# SNES_and_NES_Dumper.net
KiCad netlist of a schematic drawn in EAGLE
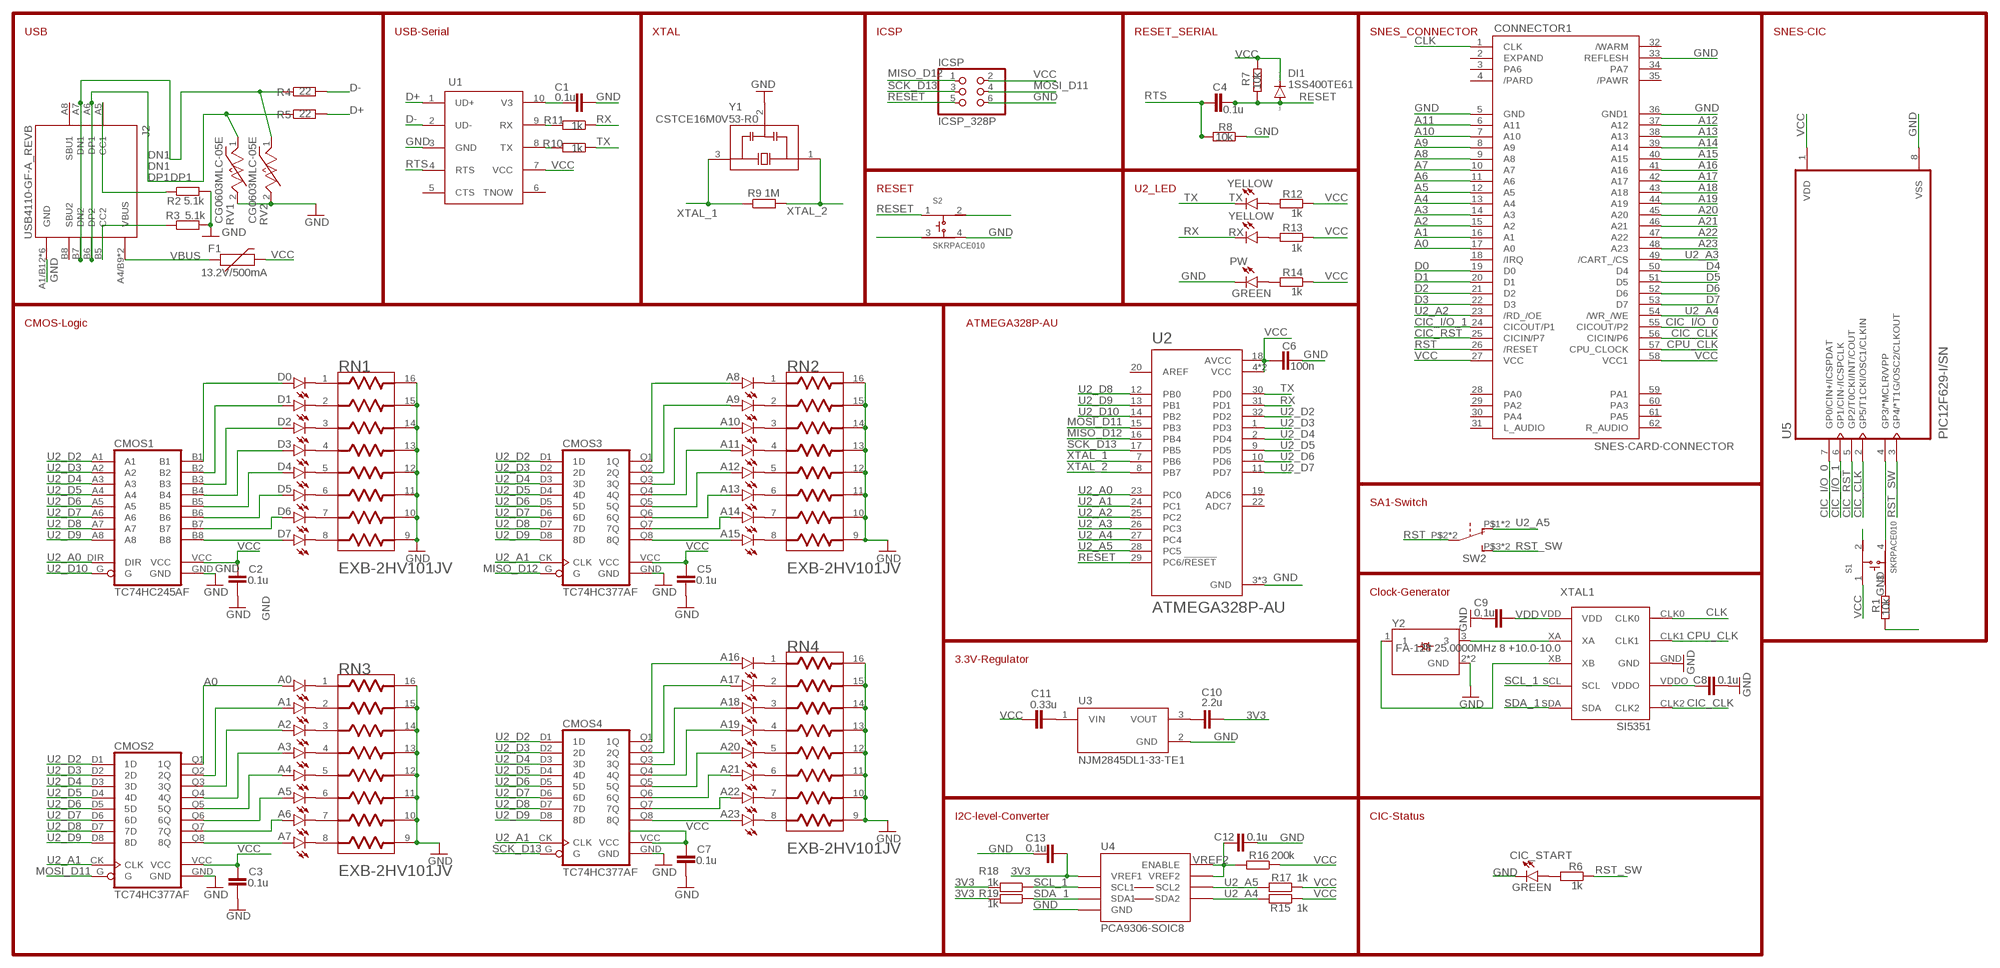
[diagram p0: schematic, sheet 1]

(export (version "E")
  (design (tool "Eeschema 10.0.6"))
  (components
    (comp (ref "A0")
      (value "YELLOW")
      (footprint "eagle-import:SML0805")
      (libsource (lib "eagle-import") (part "LEDSML0805"))
    )
    (comp (ref "A1")
      (value "YELLOW")
      (footprint "eagle-import:SML0805")
      (libsource (lib "eagle-import") (part "LEDSML0805"))
    )
    (comp (ref "A2")
      (value "YELLOW")
      (footprint "eagle-import:SML0805")
      (libsource (lib "eagle-import") (part "LEDSML0805"))
    )
    (comp (ref "A3")
      (value "YELLOW")
      (footprint "eagle-import:SML0805")
      (libsource (lib "eagle-import") (part "LEDSML0805"))
    )
    (comp (ref "A4")
      (value "YELLOW")
      (footprint "eagle-import:SML0805")
      (libsource (lib "eagle-import") (part "LEDSML0805"))
    )
    (comp (ref "A5")
      (value "YELLOW")
      (footprint "eagle-import:SML0805")
      (libsource (lib "eagle-import") (part "LEDSML0805"))
    )
    (comp (ref "A6")
      (value "YELLOW")
      (footprint "eagle-import:SML0805")
      (libsource (lib "eagle-import") (part "LEDSML0805"))
    )
    (comp (ref "A7")
      (value "YELLOW")
      (footprint "eagle-import:SML0805")
      (libsource (lib "eagle-import") (part "LEDSML0805"))
    )
    (comp (ref "A8")
      (value "YELLOW")
      (footprint "eagle-import:SML0805")
      (libsource (lib "eagle-import") (part "LEDSML0805"))
    )
    (comp (ref "A9")
      (value "YELLOW")
      (footprint "eagle-import:SML0805")
      (libsource (lib "eagle-import") (part "LEDSML0805"))
    )
    (comp (ref "A10")
      (value "YELLOW")
      (footprint "eagle-import:SML0805")
      (libsource (lib "eagle-import") (part "LEDSML0805"))
    )
    (comp (ref "A11")
      (value "YELLOW")
      (footprint "eagle-import:SML0805")
      (libsource (lib "eagle-import") (part "LEDSML0805"))
    )
    (comp (ref "A12")
      (value "YELLOW")
      (footprint "eagle-import:SML0805")
      (libsource (lib "eagle-import") (part "LEDSML0805"))
    )
    (comp (ref "A13")
      (value "YELLOW")
      (footprint "eagle-import:SML0805")
      (libsource (lib "eagle-import") (part "LEDSML0805"))
    )
    (comp (ref "A14")
      (value "YELLOW")
      (footprint "eagle-import:SML0805")
      (libsource (lib "eagle-import") (part "LEDSML0805"))
    )
    (comp (ref "A15")
      (value "YELLOW")
      (footprint "eagle-import:SML0805")
      (libsource (lib "eagle-import") (part "LEDSML0805"))
    )
    (comp (ref "A16")
      (value "YELLOW")
      (footprint "eagle-import:SML0805")
      (libsource (lib "eagle-import") (part "LEDSML0805"))
    )
    (comp (ref "A17")
      (value "YELLOW")
      (footprint "eagle-import:SML0805")
      (libsource (lib "eagle-import") (part "LEDSML0805"))
    )
    (comp (ref "A18")
      (value "YELLOW")
      (footprint "eagle-import:SML0805")
      (libsource (lib "eagle-import") (part "LEDSML0805"))
    )
    (comp (ref "A19")
      (value "YELLOW")
      (footprint "eagle-import:SML0805")
      (libsource (lib "eagle-import") (part "LEDSML0805"))
    )
    (comp (ref "A20")
      (value "YELLOW")
      (footprint "eagle-import:SML0805")
      (libsource (lib "eagle-import") (part "LEDSML0805"))
    )
    (comp (ref "A21")
      (value "YELLOW")
      (footprint "eagle-import:SML0805")
      (libsource (lib "eagle-import") (part "LEDSML0805"))
    )
    (comp (ref "A22")
      (value "YELLOW")
      (footprint "eagle-import:SML0805")
      (libsource (lib "eagle-import") (part "LEDSML0805"))
    )
    (comp (ref "A23")
      (value "YELLOW")
      (footprint "eagle-import:SML0805")
      (libsource (lib "eagle-import") (part "LEDSML0805"))
    )
    (comp (ref "C1")
      (value "0.1u")
      (footprint "eagle-import:C0603")
      (libsource (lib "eagle-import") (part "C-EUC0603"))
    )
    (comp (ref "C2")
      (value "0.1u")
      (footprint "eagle-import:C0603")
      (libsource (lib "eagle-import") (part "C-EUC0603"))
    )
    (comp (ref "C3")
      (value "0.1u")
      (footprint "eagle-import:C0603")
      (libsource (lib "eagle-import") (part "C-EUC0603"))
    )
    (comp (ref "C4")
      (value "0.1u")
      (footprint "eagle-import:C0603")
      (libsource (lib "eagle-import") (part "C-EUC0603"))
    )
    (comp (ref "C5")
      (value "0.1u")
      (footprint "eagle-import:C0603")
      (libsource (lib "eagle-import") (part "C-EUC0603"))
    )
    (comp (ref "C6")
      (value "100n")
      (footprint "eagle-import:C0603")
      (libsource (lib "eagle-import") (part "C-EUC0603"))
    )
    (comp (ref "C7")
      (value "0.1u")
      (footprint "eagle-import:C0603")
      (libsource (lib "eagle-import") (part "C-EUC0603"))
    )
    (comp (ref "C8")
      (value "0.1u")
      (footprint "eagle-import:C0603")
      (libsource (lib "eagle-import") (part "C-EUC0603"))
    )
    (comp (ref "C9")
      (value "0.1u")
      (footprint "eagle-import:C0603")
      (libsource (lib "eagle-import") (part "C-EUC0603"))
    )
    (comp (ref "C10")
      (value "2.2u")
      (footprint "eagle-import:C0603")
      (libsource (lib "eagle-import") (part "C-EUC0603"))
    )
    (comp (ref "C11")
      (value "0.33u")
      (footprint "eagle-import:C0603")
      (libsource (lib "eagle-import") (part "C-EUC0603"))
    )
    (comp (ref "C12")
      (value "0.1u")
      (footprint "eagle-import:C0603")
      (libsource (lib "eagle-import") (part "C-EUC0603"))
    )
    (comp (ref "C13")
      (value "0.1u")
      (footprint "eagle-import:C0603")
      (libsource (lib "eagle-import") (part "C-EUC0603"))
    )
    (comp (ref "CIC_START")
      (value "GREEN")
      (footprint "eagle-import:SML0805")
      (libsource (lib "eagle-import") (part "LEDSML0805"))
    )
    (comp (ref "CMOS1")
      (value "TC74HC245AF")
      (footprint "eagle-import:SO20W")
      (libsource (lib "eagle-import") (part "TC74HC245AF"))
    )
    (comp (ref "CMOS2")
      (value "TC74HC377AF")
      (footprint "eagle-import:SO20W")
      (libsource (lib "eagle-import") (part "TC74HC377AF"))
    )
    (comp (ref "CMOS3")
      (value "TC74HC377AF")
      (footprint "eagle-import:SO20W")
      (libsource (lib "eagle-import") (part "TC74HC377AF"))
    )
    (comp (ref "CMOS4")
      (value "TC74HC377AF")
      (footprint "eagle-import:SO20W")
      (libsource (lib "eagle-import") (part "TC74HC377AF"))
    )
    (comp (ref "CONNECTOR1")
      (value "SNES-CARD-CONNECTOR")
      (footprint "eagle-import:CON")
      (libsource (lib "eagle-import") (part "SNES-CARD-CONNECTOR"))
    )
    (comp (ref "D0")
      (value "YELLOW")
      (footprint "eagle-import:SML0805")
      (libsource (lib "eagle-import") (part "LEDSML0805"))
    )
    (comp (ref "D1")
      (value "YELLOW")
      (footprint "eagle-import:SML0805")
      (libsource (lib "eagle-import") (part "LEDSML0805"))
    )
    (comp (ref "D2")
      (value "YELLOW")
      (footprint "eagle-import:SML0805")
      (libsource (lib "eagle-import") (part "LEDSML0805"))
    )
    (comp (ref "D3")
      (value "YELLOW")
      (footprint "eagle-import:SML0805")
      (libsource (lib "eagle-import") (part "LEDSML0805"))
    )
    (comp (ref "D4")
      (value "YELLOW")
      (footprint "eagle-import:SML0805")
      (libsource (lib "eagle-import") (part "LEDSML0805"))
    )
    (comp (ref "D5")
      (value "YELLOW")
      (footprint "eagle-import:SML0805")
      (libsource (lib "eagle-import") (part "LEDSML0805"))
    )
    (comp (ref "D6")
      (value "YELLOW")
      (footprint "eagle-import:SML0805")
      (libsource (lib "eagle-import") (part "LEDSML0805"))
    )
    (comp (ref "D7")
      (value "YELLOW")
      (footprint "eagle-import:SML0805")
      (libsource (lib "eagle-import") (part "LEDSML0805"))
    )
    (comp (ref "DI1")
      (value "1SS400TE61")
      (footprint "eagle-import:SOD523")
      (libsource (lib "eagle-import") (part "DIODE-SOD523"))
    )
    (comp (ref "F1")
      (value "13.2V/500mA")
      (footprint "eagle-import:1206")
      (libsource (lib "eagle-import") (part "PPTC_THREE-QUARTER-AMP"))
    )
    (comp (ref "ICSP")
      (value "ICSP_328P")
      (footprint "eagle-import:2X03")
      (libsource (lib "eagle-import") (part "PINHD-2X3"))
    )
    (comp (ref "J2")
      (value "USB4110-GF-A_REVB")
      (footprint "eagle-import:GCT_USB4110-GF-A_REVB")
      (fields (field (name "MF") "GCT") (field (name "MP") "USB4110-GF-A"))
      (libsource (lib "eagle-import") (part "USB4110-GF-A_REVB"))
    )
    (comp (ref "PW")
      (value "GREEN")
      (footprint "eagle-import:SML0805")
      (libsource (lib "eagle-import") (part "LEDSML0805"))
    )
    (comp (ref "R1")
      (value "10k")
      (footprint "eagle-import:R0603")
      (libsource (lib "eagle-import") (part "R-EU_R0603"))
    )
    (comp (ref "R2")
      (value "5.1k")
      (footprint "eagle-import:R0603")
      (libsource (lib "eagle-import") (part "R-EU_R0603"))
    )
    (comp (ref "R3")
      (value "5.1k")
      (footprint "eagle-import:R0603")
      (libsource (lib "eagle-import") (part "R-EU_R0603"))
    )
    (comp (ref "R4")
      (value "22")
      (footprint "eagle-import:R0603")
      (libsource (lib "eagle-import") (part "R-EU_R0603"))
    )
    (comp (ref "R5")
      (value "22")
      (footprint "eagle-import:R0603")
      (libsource (lib "eagle-import") (part "R-EU_R0603"))
    )
    (comp (ref "R6")
      (value "1k")
      (footprint "eagle-import:R0603")
      (libsource (lib "eagle-import") (part "R-EU_R0603"))
    )
    (comp (ref "R7")
      (value "10k")
      (footprint "eagle-import:R0603")
      (libsource (lib "eagle-import") (part "R-EU_R0603"))
    )
    (comp (ref "R8")
      (value "10k")
      (footprint "eagle-import:R0603")
      (libsource (lib "eagle-import") (part "R-EU_R0603"))
    )
    (comp (ref "R9")
      (value "1M")
      (footprint "eagle-import:R0603")
      (libsource (lib "eagle-import") (part "R-EU_R0603"))
    )
    (comp (ref "R10")
      (value "1k")
      (footprint "eagle-import:R0603")
      (libsource (lib "eagle-import") (part "R-EU_R0603"))
    )
    (comp (ref "R11")
      (value "1k")
      (footprint "eagle-import:R0603")
      (libsource (lib "eagle-import") (part "R-EU_R0603"))
    )
    (comp (ref "R12")
      (value "1k")
      (footprint "eagle-import:R0603")
      (libsource (lib "eagle-import") (part "R-EU_R0603"))
    )
    (comp (ref "R13")
      (value "1k")
      (footprint "eagle-import:R0603")
      (libsource (lib "eagle-import") (part "R-EU_R0603"))
    )
    (comp (ref "R14")
      (value "1k")
      (footprint "eagle-import:R0603")
      (libsource (lib "eagle-import") (part "R-EU_R0603"))
    )
    (comp (ref "R15")
      (value "1k")
      (footprint "eagle-import:R0603")
      (libsource (lib "eagle-import") (part "R-EU_R0603"))
    )
    (comp (ref "R16")
      (value "200k")
      (footprint "eagle-import:R0603")
      (libsource (lib "eagle-import") (part "R-EU_R0603"))
    )
    (comp (ref "R17")
      (value "1k")
      (footprint "eagle-import:R0603")
      (libsource (lib "eagle-import") (part "R-EU_R0603"))
    )
    (comp (ref "R18")
      (value "1k")
      (footprint "eagle-import:R0603")
      (libsource (lib "eagle-import") (part "R-EU_R0603"))
    )
    (comp (ref "R19")
      (value "1k")
      (footprint "eagle-import:R0603")
      (libsource (lib "eagle-import") (part "R-EU_R0603"))
    )
    (comp (ref "RN1")
      (value "PANASONIC_EXB-2HV101JVPANASONIC_EXB-2HV101JV_0_0")
      (footprint "eagle-import:PANASONIC_EXB-2HV101JV_0")
      (fields
        (field (name "DIGIKEY_PART_NUMBER") "Y1101CT-ND")
        (field (name "MF") "Panasonic")
        (field (name "MOUSER_PART_NUMBER") "667-EXB-2HV101JV")
      )
      (libsource (lib "eagle-import") (part "PANASONIC_EXB-2HV101JVPANASONIC_EXB-2HV101JV_0_0"))
    )
    (comp (ref "RN2")
      (value "PANASONIC_EXB-2HV101JVPANASONIC_EXB-2HV101JV_0_0")
      (footprint "eagle-import:PANASONIC_EXB-2HV101JV_0")
      (fields
        (field (name "DIGIKEY_PART_NUMBER") "Y1101CT-ND")
        (field (name "MF") "Panasonic")
        (field (name "MOUSER_PART_NUMBER") "667-EXB-2HV101JV")
      )
      (libsource (lib "eagle-import") (part "PANASONIC_EXB-2HV101JVPANASONIC_EXB-2HV101JV_0_0"))
    )
    (comp (ref "RN3")
      (value "PANASONIC_EXB-2HV101JVPANASONIC_EXB-2HV101JV_0_0")
      (footprint "eagle-import:PANASONIC_EXB-2HV101JV_0")
      (fields
        (field (name "DIGIKEY_PART_NUMBER") "Y1101CT-ND")
        (field (name "MF") "Panasonic")
        (field (name "MOUSER_PART_NUMBER") "667-EXB-2HV101JV")
      )
      (libsource (lib "eagle-import") (part "PANASONIC_EXB-2HV101JVPANASONIC_EXB-2HV101JV_0_0"))
    )
    (comp (ref "RN4")
      (value "PANASONIC_EXB-2HV101JVPANASONIC_EXB-2HV101JV_0_0")
      (footprint "eagle-import:PANASONIC_EXB-2HV101JV_0")
      (fields
        (field (name "DIGIKEY_PART_NUMBER") "Y1101CT-ND")
        (field (name "MF") "Panasonic")
        (field (name "MOUSER_PART_NUMBER") "667-EXB-2HV101JV")
      )
      (libsource (lib "eagle-import") (part "PANASONIC_EXB-2HV101JVPANASONIC_EXB-2HV101JV_0_0"))
    )
    (comp (ref "RV1")
      (value "CG0603MLC-05E")
      (footprint "eagle-import:VARC1608X56N")
      (fields (field (name "MF") "Bourns"))
      (libsource (lib "eagle-import") (part "CG0603MLC-05E"))
    )
    (comp (ref "RV2")
      (value "CG0603MLC-05E")
      (footprint "eagle-import:VARC1608X56N")
      (fields (field (name "MF") "Bourns"))
      (libsource (lib "eagle-import") (part "CG0603MLC-05E"))
    )
    (comp (ref "RX")
      (value "YELLOW")
      (footprint "eagle-import:SML0805")
      (libsource (lib "eagle-import") (part "LEDSML0805"))
    )
    (comp (ref "S1")
      (value "SKRPACE010")
      (footprint "eagle-import:SW_SKRPACE010")
      (fields (field (name "MF") "ALPS"))
      (libsource (lib "eagle-import") (part "SKRPACE010"))
    )
    (comp (ref "S2")
      (value "SKRPACE010")
      (footprint "eagle-import:SW_SKRPACE010")
      (fields (field (name "MF") "ALPS"))
      (libsource (lib "eagle-import") (part "SKRPACE010"))
    )
    (comp (ref "SW2")
      (value "ALPS_SSSS213202")
      (footprint "eagle-import:ALPS_SSSS213202")
      (libsource (lib "eagle-import") (part "ALPS_SSSS213202"))
    )
    (comp (ref "TX")
      (value "YELLOW")
      (footprint "eagle-import:SML0805")
      (libsource (lib "eagle-import") (part "LEDSML0805"))
    )
    (comp (ref "U1")
      (value "CH340E")
      (footprint "eagle-import:MSOP10")
      (fields (field (name "MF") "WCH"))
      (libsource (lib "eagle-import") (part "CH340ESMD"))
    )
    (comp (ref "U2")
      (value "ATMEGA328P-AU")
      (footprint "eagle-import:QFP80P900X900X120-32N")
      (fields (field (name "MF") "Microchip Technology"))
      (libsource (lib "eagle-import") (part "ATMEGA328P-AU"))
    )
    (comp (ref "U3")
      (value "NJM2845DL1-33-TE1")
      (footprint "eagle-import:DPAK228P968X238-4N")
      (fields (field (name "MF") "NJR Corporation/NJRC"))
      (libsource (lib "eagle-import") (part "NJM2845DL1-33-TE1"))
    )
    (comp (ref "U4")
      (value "PCA9306-SOIC8")
      (footprint "eagle-import:SOIC-8")
      (libsource (lib "eagle-import") (part "IC2_LEVEL_TRANSLATER"))
    )
    (comp (ref "U5")
      (value "PIC12F629-I/SN")
      (footprint "eagle-import:SOIC127P600X175-8N")
      (fields (field (name "MF") "Microchip"))
      (libsource (lib "eagle-import") (part "PIC12F629-I/SN"))
    )
    (comp (ref "XTAL1")
      (value "SI5351")
      (footprint "eagle-import:SI5351A-B-GTR")
      (libsource (lib "eagle-import") (part "SI5351A-B-GTR"))
    )
    (comp (ref "Y1")
      (value "CSTCE16M0V53-R0")
      (footprint "eagle-import:OSC_CSTCE16M0V53-R0")
      (fields (field (name "MF") "Murata"))
      (libsource (lib "eagle-import") (part "CSTCE16M0V53-R0"))
    )
    (comp (ref "Y2")
      (value "FA-128 25.0000MHz 8 +10.0-10.0")
      (footprint "eagle-import:OSCSC320X250X100N")
      (fields (field (name "MF") "Abracon") (field (name "MP") "ABM8X-102-32.000MHZ-T"))
      (libsource (lib "eagle-import") (part "ABM8X-102-32.000MHZ-T"))
    )
  )
  (nets
    (net (code "1") (name "/3V3") (class "Default")
      (node (ref "C10") (pin "2") (pinfunction "2_2") (pintype "passive"))
      (node (ref "C13") (pin "2") (pinfunction "2_2") (pintype "passive"))
      (node (ref "R18") (pin "2") (pinfunction "2_2") (pintype "passive"))
      (node (ref "R19") (pin "2") (pinfunction "2_2") (pintype "passive"))
      (node (ref "U4") (pin "1") (pinfunction "VREF1_1") (pintype "power_in"))
    )
    (net (code "2") (name "/A0") (class "Default")
      (node (ref "A0") (pin "A") (pinfunction "A_A") (pintype "passive"))
      (node (ref "CMOS2") (pin "Q1") (pinfunction "1Q_Q1") (pintype "output"))
      (node (ref "CONNECTOR1") (pin "17") (pinfunction "A0_17") (pintype "bidirectional"))
    )
    (net (code "3") (name "/A1") (class "Default")
      (node (ref "A1") (pin "A") (pinfunction "A_A") (pintype "passive"))
      (node (ref "CMOS2") (pin "Q2") (pinfunction "2Q_Q2") (pintype "output"))
      (node (ref "CONNECTOR1") (pin "16") (pinfunction "A1_16") (pintype "bidirectional"))
    )
    (net (code "4") (name "/A2") (class "Default")
      (node (ref "A2") (pin "A") (pinfunction "A_A") (pintype "passive"))
      (node (ref "CMOS2") (pin "Q3") (pinfunction "3Q_Q3") (pintype "output"))
      (node (ref "CONNECTOR1") (pin "15") (pinfunction "A2_15") (pintype "bidirectional"))
    )
    (net (code "5") (name "/A3") (class "Default")
      (node (ref "A3") (pin "A") (pinfunction "A_A") (pintype "passive"))
      (node (ref "CMOS2") (pin "Q4") (pinfunction "4Q_Q4") (pintype "output"))
      (node (ref "CONNECTOR1") (pin "14") (pinfunction "A3_14") (pintype "bidirectional"))
    )
    (net (code "6") (name "/A4") (class "Default")
      (node (ref "A4") (pin "A") (pinfunction "A_A") (pintype "passive"))
      (node (ref "CMOS2") (pin "Q5") (pinfunction "5Q_Q5") (pintype "output"))
      (node (ref "CONNECTOR1") (pin "13") (pinfunction "A4_13") (pintype "bidirectional"))
    )
    (net (code "7") (name "/A5") (class "Default")
      (node (ref "A5") (pin "A") (pinfunction "A_A") (pintype "passive"))
      (node (ref "CMOS2") (pin "Q6") (pinfunction "6Q_Q6") (pintype "output"))
      (node (ref "CONNECTOR1") (pin "12") (pinfunction "A5_12") (pintype "bidirectional"))
    )
    (net (code "8") (name "/A6") (class "Default")
      (node (ref "A6") (pin "A") (pinfunction "A_A") (pintype "passive"))
      (node (ref "CMOS2") (pin "Q7") (pinfunction "7Q_Q7") (pintype "output"))
      (node (ref "CONNECTOR1") (pin "11") (pinfunction "A6_11") (pintype "bidirectional"))
    )
    (net (code "9") (name "/A7") (class "Default")
      (node (ref "A7") (pin "A") (pinfunction "A_A") (pintype "passive"))
      (node (ref "CMOS2") (pin "Q8") (pinfunction "8Q_Q8") (pintype "output"))
      (node (ref "CONNECTOR1") (pin "10") (pinfunction "A7_10") (pintype "bidirectional"))
    )
    (net (code "10") (name "/A8") (class "Default")
      (node (ref "A8") (pin "A") (pinfunction "A_A") (pintype "passive"))
      (node (ref "CMOS3") (pin "Q1") (pinfunction "1Q_Q1") (pintype "output"))
      (node (ref "CONNECTOR1") (pin "9") (pinfunction "A8_9") (pintype "bidirectional"))
    )
    (net (code "11") (name "/A9") (class "Default")
      (node (ref "A9") (pin "A") (pinfunction "A_A") (pintype "passive"))
      (node (ref "CMOS3") (pin "Q2") (pinfunction "2Q_Q2") (pintype "output"))
      (node (ref "CONNECTOR1") (pin "8") (pinfunction "A9_8") (pintype "bidirectional"))
    )
    (net (code "12") (name "/A10") (class "Default")
      (node (ref "A10") (pin "A") (pinfunction "A_A") (pintype "passive"))
      (node (ref "CMOS3") (pin "Q3") (pinfunction "3Q_Q3") (pintype "output"))
      (node (ref "CONNECTOR1") (pin "7") (pinfunction "A10_7") (pintype "bidirectional"))
    )
    (net (code "13") (name "/A11") (class "Default")
      (node (ref "A11") (pin "A") (pinfunction "A_A") (pintype "passive"))
      (node (ref "CMOS3") (pin "Q4") (pinfunction "4Q_Q4") (pintype "output"))
      (node (ref "CONNECTOR1") (pin "6") (pinfunction "A11_6") (pintype "bidirectional"))
    )
    (net (code "14") (name "/A12") (class "Default")
      (node (ref "A12") (pin "A") (pinfunction "A_A") (pintype "passive"))
      (node (ref "CMOS3") (pin "Q5") (pinfunction "5Q_Q5") (pintype "output"))
      (node (ref "CONNECTOR1") (pin "37") (pinfunction "A12_37") (pintype "bidirectional"))
    )
    (net (code "15") (name "/A13") (class "Default")
      (node (ref "A13") (pin "A") (pinfunction "A_A") (pintype "passive"))
      (node (ref "CMOS3") (pin "Q6") (pinfunction "6Q_Q6") (pintype "output"))
      (node (ref "CONNECTOR1") (pin "38") (pinfunction "A13_38") (pintype "bidirectional"))
    )
    (net (code "16") (name "/A14") (class "Default")
      (node (ref "A14") (pin "A") (pinfunction "A_A") (pintype "passive"))
      (node (ref "CMOS3") (pin "Q7") (pinfunction "7Q_Q7") (pintype "output"))
      (node (ref "CONNECTOR1") (pin "39") (pinfunction "A14_39") (pintype "bidirectional"))
    )
    (net (code "17") (name "/A15") (class "Default")
      (node (ref "A15") (pin "A") (pinfunction "A_A") (pintype "passive"))
      (node (ref "CMOS3") (pin "Q8") (pinfunction "8Q_Q8") (pintype "output"))
      (node (ref "CONNECTOR1") (pin "40") (pinfunction "A15_40") (pintype "bidirectional"))
    )
    (net (code "18") (name "/A16") (class "Default")
      (node (ref "A16") (pin "A") (pinfunction "A_A") (pintype "passive"))
      (node (ref "CMOS4") (pin "Q1") (pinfunction "1Q_Q1") (pintype "output"))
      (node (ref "CONNECTOR1") (pin "41") (pinfunction "A16_41") (pintype "bidirectional"))
    )
    (net (code "19") (name "/A17") (class "Default")
      (node (ref "A17") (pin "A") (pinfunction "A_A") (pintype "passive"))
      (node (ref "CMOS4") (pin "Q2") (pinfunction "2Q_Q2") (pintype "output"))
      (node (ref "CONNECTOR1") (pin "42") (pinfunction "A17_42") (pintype "bidirectional"))
    )
    (net (code "20") (name "/A18") (class "Default")
      (node (ref "A18") (pin "A") (pinfunction "A_A") (pintype "passive"))
      (node (ref "CMOS4") (pin "Q3") (pinfunction "3Q_Q3") (pintype "output"))
      (node (ref "CONNECTOR1") (pin "43") (pinfunction "A18_43") (pintype "bidirectional"))
    )
    (net (code "21") (name "/A19") (class "Default")
      (node (ref "A19") (pin "A") (pinfunction "A_A") (pintype "passive"))
      (node (ref "CMOS4") (pin "Q4") (pinfunction "4Q_Q4") (pintype "output"))
      (node (ref "CONNECTOR1") (pin "44") (pinfunction "A19_44") (pintype "bidirectional"))
    )
    (net (code "22") (name "/A20") (class "Default")
      (node (ref "A20") (pin "A") (pinfunction "A_A") (pintype "passive"))
      (node (ref "CMOS4") (pin "Q5") (pinfunction "5Q_Q5") (pintype "output"))
      (node (ref "CONNECTOR1") (pin "45") (pinfunction "A20_45") (pintype "bidirectional"))
    )
    (net (code "23") (name "/A21") (class "Default")
      (node (ref "A21") (pin "A") (pinfunction "A_A") (pintype "passive"))
      (node (ref "CMOS4") (pin "Q6") (pinfunction "6Q_Q6") (pintype "output"))
      (node (ref "CONNECTOR1") (pin "46") (pinfunction "A21_46") (pintype "bidirectional"))
    )
    (net (code "24") (name "/A22") (class "Default")
      (node (ref "A22") (pin "A") (pinfunction "A_A") (pintype "passive"))
      (node (ref "CMOS4") (pin "Q7") (pinfunction "7Q_Q7") (pintype "output"))
      (node (ref "CONNECTOR1") (pin "47") (pinfunction "A22_47") (pintype "bidirectional"))
    )
    (net (code "25") (name "/A23") (class "Default")
      (node (ref "A23") (pin "A") (pinfunction "A_A") (pintype "passive"))
      (node (ref "CMOS4") (pin "Q8") (pinfunction "8Q_Q8") (pintype "output"))
      (node (ref "CONNECTOR1") (pin "48") (pinfunction "A23_48") (pintype "bidirectional"))
    )
    (net (code "26") (name "/CIC_CLK") (class "Default")
      (node (ref "CONNECTOR1") (pin "56") (pinfunction "CICIN/P6_56") (pintype "bidirectional"))
      (node (ref "U5") (pin "2") (pinfunction "GP5/T1CKI/OSC1/CLKIN_2") (pintype "input"))
      (node (ref "XTAL1") (pin "CLK2") (pinfunction "CLK2_CLK2") (pintype "bidirectional"))
    )
    (net (code "27") (name "/CIC_I{slash}O_0") (class "Default")
      (node (ref "CONNECTOR1") (pin "55") (pinfunction "CICOUT/P2_55") (pintype "bidirectional"))
      (node (ref "U5") (pin "7") (pinfunction "GP0/CIN+/ICSPDAT_7") (pintype "input"))
    )
    (net (code "28") (name "/CIC_I{slash}O_1") (class "Default")
      (node (ref "CONNECTOR1") (pin "24") (pinfunction "CICOUT/P1_24") (pintype "bidirectional"))
      (node (ref "U5") (pin "6") (pinfunction "GP1/CIN-/ICSPCLK_6") (pintype "input"))
    )
    (net (code "29") (name "/CIC_RST") (class "Default")
      (node (ref "CONNECTOR1") (pin "25") (pinfunction "CICIN/P7_25") (pintype "bidirectional"))
      (node (ref "U5") (pin "5") (pinfunction "GP2/T0CKI/INT/COUT_5") (pintype "input"))
    )
    (net (code "30") (name "/CLK") (class "Default")
      (node (ref "CONNECTOR1") (pin "1") (pinfunction "CLK_1") (pintype "bidirectional"))
      (node (ref "XTAL1") (pin "CLK0") (pinfunction "CLK0_CLK0") (pintype "bidirectional"))
    )
    (net (code "31") (name "/CPU_CLK") (class "Default")
      (node (ref "CONNECTOR1") (pin "57") (pinfunction "CPU_CLOCK_57") (pintype "bidirectional"))
      (node (ref "XTAL1") (pin "CLK1") (pinfunction "CLK1_CLK1") (pintype "bidirectional"))
    )
    (net (code "32") (name "/D+") (class "Default")
      (node (ref "R5") (pin "2") (pinfunction "2_2") (pintype "passive"))
      (node (ref "U1") (pin "1") (pinfunction "UD+_1") (pintype "bidirectional"))
    )
    (net (code "33") (name "/D-") (class "Default")
      (node (ref "R4") (pin "2") (pinfunction "2_2") (pintype "passive"))
      (node (ref "U1") (pin "2") (pinfunction "UD-_2") (pintype "bidirectional"))
    )
    (net (code "34") (name "/D0") (class "Default")
      (node (ref "CMOS1") (pin "B1") (pinfunction "B1_B1") (pintype "bidirectional"))
      (node (ref "CONNECTOR1") (pin "19") (pinfunction "D0_19") (pintype "bidirectional"))
      (node (ref "D0") (pin "A") (pinfunction "A_A") (pintype "passive"))
    )
    (net (code "35") (name "/D1") (class "Default")
      (node (ref "CMOS1") (pin "B2") (pinfunction "B2_B2") (pintype "bidirectional"))
      (node (ref "CONNECTOR1") (pin "20") (pinfunction "D1_20") (pintype "bidirectional"))
      (node (ref "D1") (pin "A") (pinfunction "A_A") (pintype "passive"))
    )
    (net (code "36") (name "/D2") (class "Default")
      (node (ref "CMOS1") (pin "B3") (pinfunction "B3_B3") (pintype "bidirectional"))
      (node (ref "CONNECTOR1") (pin "21") (pinfunction "D2_21") (pintype "bidirectional"))
      (node (ref "D2") (pin "A") (pinfunction "A_A") (pintype "passive"))
    )
    (net (code "37") (name "/D3") (class "Default")
      (node (ref "CMOS1") (pin "B4") (pinfunction "B4_B4") (pintype "bidirectional"))
      (node (ref "CONNECTOR1") (pin "22") (pinfunction "D3_22") (pintype "bidirectional"))
      (node (ref "D3") (pin "A") (pinfunction "A_A") (pintype "passive"))
    )
    (net (code "38") (name "/D4") (class "Default")
      (node (ref "CMOS1") (pin "B5") (pinfunction "B5_B5") (pintype "bidirectional"))
      (node (ref "CONNECTOR1") (pin "50") (pinfunction "D4_50") (pintype "bidirectional"))
      (node (ref "D4") (pin "A") (pinfunction "A_A") (pintype "passive"))
    )
    (net (code "39") (name "/D5") (class "Default")
      (node (ref "CMOS1") (pin "B6") (pinfunction "B6_B6") (pintype "bidirectional"))
      (node (ref "CONNECTOR1") (pin "51") (pinfunction "D5_51") (pintype "bidirectional"))
      (node (ref "D5") (pin "A") (pinfunction "A_A") (pintype "passive"))
    )
    (net (code "40") (name "/D6") (class "Default")
      (node (ref "CMOS1") (pin "B7") (pinfunction "B7_B7") (pintype "bidirectional"))
      (node (ref "CONNECTOR1") (pin "52") (pinfunction "D6_52") (pintype "bidirectional"))
      (node (ref "D6") (pin "A") (pinfunction "A_A") (pintype "passive"))
    )
    (net (code "41") (name "/D7") (class "Default")
      (node (ref "CMOS1") (pin "B8") (pinfunction "B8_B8") (pintype "bidirectional"))
      (node (ref "CONNECTOR1") (pin "53") (pinfunction "D7_53") (pintype "bidirectional"))
      (node (ref "D7") (pin "A") (pinfunction "A_A") (pintype "passive"))
    )
    (net (code "42") (name "/DN1") (class "Default")
      (node (ref "J2") (pin "A7") (pinfunction "DN1_A7") (pintype "bidirectional"))
      (node (ref "J2") (pin "B7") (pinfunction "DN2_B7") (pintype "bidirectional"))
      (node (ref "R4") (pin "1") (pinfunction "1_1") (pintype "passive"))
      (node (ref "RV2") (pin "1") (pinfunction "1_1") (pintype "passive"))
    )
    (net (code "43") (name "/DP1") (class "Default")
      (node (ref "J2") (pin "A6") (pinfunction "DP1_A6") (pintype "bidirectional"))
      (node (ref "J2") (pin "B6") (pinfunction "DP2_B6") (pintype "bidirectional"))
      (node (ref "R5") (pin "1") (pinfunction "1_1") (pintype "passive"))
      (node (ref "RV1") (pin "1") (pinfunction "1_1") (pintype "passive"))
    )
    (net (code "44") (name "/MISO_D12") (class "Default")
      (node (ref "CMOS3") (pin "G") (pinfunction "G_G") (pintype "input"))
      (node (ref "ICSP") (pin "1") (pinfunction "1_1") (pintype "passive"))
      (node (ref "U2") (pin "16") (pinfunction "PB4_16") (pintype "bidirectional"))
    )
    (net (code "45") (name "/MOSI_D11") (class "Default")
      (node (ref "CMOS2") (pin "G") (pinfunction "G_G") (pintype "input"))
      (node (ref "ICSP") (pin "4") (pinfunction "4_4") (pintype "passive"))
      (node (ref "U2") (pin "15") (pinfunction "PB3_15") (pintype "bidirectional"))
    )
    (net (code "46") (name "/RESET") (class "Default")
      (node (ref "C4") (pin "2") (pinfunction "2_2") (pintype "passive"))
      (node (ref "DI1") (pin "A") (pinfunction "A_A") (pintype "passive"))
      (node (ref "ICSP") (pin "5") (pinfunction "5_5") (pintype "passive"))
      (node (ref "R7") (pin "1") (pinfunction "1_1") (pintype "passive"))
      (node (ref "S2") (pin "1") (pinfunction "1_1") (pintype "bidirectional"))
      (node (ref "S2") (pin "2") (pinfunction "2_2") (pintype "bidirectional"))
      (node (ref "U2") (pin "29") (pinfunction "PC6/~{RESET}_29") (pintype "bidirectional"))
    )
    (net (code "47") (name "/RST") (class "Default")
      (node (ref "CONNECTOR1") (pin "26") (pinfunction "/RESET_26") (pintype "bidirectional"))
      (node (ref "SW2") (pin "P$2") (pinfunction "2_P$2") (pintype "passive"))
      (node (ref "SW2") (pin "P$5") (pinfunction "2_P$5") (pintype "passive"))
    )
    (net (code "48") (name "/RST_SW") (class "Default")
      (node (ref "R6") (pin "1") (pinfunction "1_1") (pintype "passive"))
      (node (ref "SW2") (pin "P$3") (pinfunction "3_P$3") (pintype "passive"))
      (node (ref "SW2") (pin "P$4") (pinfunction "3_P$4") (pintype "passive"))
      (node (ref "U5") (pin "3") (pinfunction "GP4/*T1G/OSC2/CLKOUT_3") (pintype "bidirectional"))
    )
    (net (code "49") (name "/RTS") (class "Default")
      (node (ref "C4") (pin "1") (pinfunction "1_1") (pintype "passive"))
      (node (ref "R8") (pin "2") (pinfunction "2_2") (pintype "passive"))
      (node (ref "U1") (pin "4") (pinfunction "RTS_4") (pintype "output"))
    )
    (net (code "50") (name "/RX") (class "Default")
      (node (ref "R11") (pin "1") (pinfunction "1_1") (pintype "passive"))
      (node (ref "RX") (pin "C") (pinfunction "C_C") (pintype "passive"))
      (node (ref "U2") (pin "31") (pinfunction "PD1_31") (pintype "bidirectional"))
    )
    (net (code "51") (name "/SCK_D13") (class "Default")
      (node (ref "CMOS4") (pin "G") (pinfunction "G_G") (pintype "input"))
      (node (ref "ICSP") (pin "3") (pinfunction "3_3") (pintype "passive"))
      (node (ref "U2") (pin "17") (pinfunction "PB5_17") (pintype "bidirectional"))
    )
    (net (code "52") (name "/SCL_1") (class "Default")
      (node (ref "R18") (pin "1") (pinfunction "1_1") (pintype "passive"))
      (node (ref "U4") (pin "2") (pinfunction "SCL1_2") (pintype "bidirectional"))
      (node (ref "XTAL1") (pin "SCL") (pinfunction "SCL_SCL") (pintype "bidirectional"))
    )
    (net (code "53") (name "/SDA_1") (class "Default")
      (node (ref "R19") (pin "1") (pinfunction "1_1") (pintype "passive"))
      (node (ref "U4") (pin "3") (pinfunction "SDA1_3") (pintype "bidirectional"))
      (node (ref "XTAL1") (pin "SDA") (pinfunction "SDA_SDA") (pintype "bidirectional"))
    )
    (net (code "54") (name "/TX") (class "Default")
      (node (ref "R10") (pin "1") (pinfunction "1_1") (pintype "passive"))
      (node (ref "TX") (pin "C") (pinfunction "C_C") (pintype "passive"))
      (node (ref "U2") (pin "30") (pinfunction "PD0_30") (pintype "bidirectional"))
    )
    (net (code "55") (name "/U2_A0") (class "Default")
      (node (ref "CMOS1") (pin "DIR") (pinfunction "DIR_DIR") (pintype "input"))
      (node (ref "U2") (pin "23") (pinfunction "PC0_23") (pintype "bidirectional"))
    )
    (net (code "56") (name "/U2_A1") (class "Default")
      (node (ref "CMOS2") (pin "CK") (pinfunction "CLK_CK") (pintype "input"))
      (node (ref "CMOS3") (pin "CK") (pinfunction "CLK_CK") (pintype "input"))
      (node (ref "CMOS4") (pin "CK") (pinfunction "CLK_CK") (pintype "input"))
      (node (ref "U2") (pin "24") (pinfunction "PC1_24") (pintype "bidirectional"))
    )
    (net (code "57") (name "/U2_A2") (class "Default")
      (node (ref "CONNECTOR1") (pin "23") (pinfunction "/RD_/OE_23") (pintype "bidirectional"))
      (node (ref "U2") (pin "25") (pinfunction "PC2_25") (pintype "bidirectional"))
    )
    (net (code "58") (name "/U2_A3") (class "Default")
      (node (ref "CONNECTOR1") (pin "49") (pinfunction "/CART_/CS_49") (pintype "bidirectional"))
      (node (ref "U2") (pin "26") (pinfunction "PC3_26") (pintype "bidirectional"))
    )
    (net (code "59") (name "/U2_A4") (class "Default")
      (node (ref "CONNECTOR1") (pin "54") (pinfunction "/WR_/WE_54") (pintype "bidirectional"))
      (node (ref "R15") (pin "2") (pinfunction "2_2") (pintype "passive"))
      (node (ref "U2") (pin "27") (pinfunction "PC4_27") (pintype "bidirectional"))
      (node (ref "U4") (pin "5") (pinfunction "SDA2_5") (pintype "bidirectional"))
    )
    (net (code "60") (name "/U2_A5") (class "Default")
      (node (ref "R17") (pin "2") (pinfunction "2_2") (pintype "passive"))
      (node (ref "SW2") (pin "P$1") (pinfunction "1_P$1") (pintype "passive"))
      (node (ref "SW2") (pin "P$6") (pinfunction "1_P$6") (pintype "passive"))
      (node (ref "U2") (pin "28") (pinfunction "PC5_28") (pintype "bidirectional"))
      (node (ref "U4") (pin "6") (pinfunction "SCL2_6") (pintype "bidirectional"))
    )
    (net (code "61") (name "/U2_D2") (class "Default")
      (node (ref "CMOS1") (pin "A1") (pinfunction "A1_A1") (pintype "bidirectional"))
      (node (ref "CMOS2") (pin "D1") (pinfunction "1D_D1") (pintype "input"))
      (node (ref "CMOS3") (pin "D1") (pinfunction "1D_D1") (pintype "input"))
      (node (ref "CMOS4") (pin "D1") (pinfunction "1D_D1") (pintype "input"))
      (node (ref "U2") (pin "32") (pinfunction "PD2_32") (pintype "bidirectional"))
    )
    (net (code "62") (name "/U2_D3") (class "Default")
      (node (ref "CMOS1") (pin "A2") (pinfunction "A2_A2") (pintype "bidirectional"))
      (node (ref "CMOS2") (pin "D2") (pinfunction "2D_D2") (pintype "input"))
      (node (ref "CMOS3") (pin "D2") (pinfunction "2D_D2") (pintype "input"))
      (node (ref "CMOS4") (pin "D2") (pinfunction "2D_D2") (pintype "input"))
      (node (ref "U2") (pin "1") (pinfunction "PD3_1") (pintype "bidirectional"))
    )
    (net (code "63") (name "/U2_D4") (class "Default")
      (node (ref "CMOS1") (pin "A3") (pinfunction "A3_A3") (pintype "bidirectional"))
      (node (ref "CMOS2") (pin "D3") (pinfunction "3D_D3") (pintype "input"))
      (node (ref "CMOS3") (pin "D3") (pinfunction "3D_D3") (pintype "input"))
      (node (ref "CMOS4") (pin "D3") (pinfunction "3D_D3") (pintype "input"))
      (node (ref "U2") (pin "2") (pinfunction "PD4_2") (pintype "bidirectional"))
    )
    (net (code "64") (name "/U2_D5") (class "Default")
      (node (ref "CMOS1") (pin "A4") (pinfunction "A4_A4") (pintype "bidirectional"))
      (node (ref "CMOS2") (pin "D4") (pinfunction "4D_D4") (pintype "input"))
      (node (ref "CMOS3") (pin "D4") (pinfunction "4D_D4") (pintype "input"))
      (node (ref "CMOS4") (pin "D4") (pinfunction "4D_D4") (pintype "input"))
      (node (ref "U2") (pin "9") (pinfunction "PD5_9") (pintype "bidirectional"))
    )
    (net (code "65") (name "/U2_D6") (class "Default")
      (node (ref "CMOS1") (pin "A5") (pinfunction "A5_A5") (pintype "bidirectional"))
      (node (ref "CMOS2") (pin "D5") (pinfunction "5D_D5") (pintype "input"))
      (node (ref "CMOS3") (pin "D5") (pinfunction "5D_D5") (pintype "input"))
      (node (ref "CMOS4") (pin "D5") (pinfunction "5D_D5") (pintype "input"))
      (node (ref "U2") (pin "10") (pinfunction "PD6_10") (pintype "bidirectional"))
    )
    (net (code "66") (name "/U2_D7") (class "Default")
      (node (ref "CMOS1") (pin "A6") (pinfunction "A6_A6") (pintype "bidirectional"))
      (node (ref "CMOS2") (pin "D6") (pinfunction "6D_D6") (pintype "input"))
      (node (ref "CMOS3") (pin "D6") (pinfunction "6D_D6") (pintype "input"))
      (node (ref "CMOS4") (pin "D6") (pinfunction "6D_D6") (pintype "input"))
      (node (ref "U2") (pin "11") (pinfunction "PD7_11") (pintype "bidirectional"))
    )
    (net (code "67") (name "/U2_D8") (class "Default")
      (node (ref "CMOS1") (pin "A7") (pinfunction "A7_A7") (pintype "bidirectional"))
      (node (ref "CMOS2") (pin "D7") (pinfunction "7D_D7") (pintype "input"))
      (node (ref "CMOS3") (pin "D7") (pinfunction "7D_D7") (pintype "input"))
      (node (ref "CMOS4") (pin "D7") (pinfunction "7D_D7") (pintype "input"))
      (node (ref "U2") (pin "12") (pinfunction "PB0_12") (pintype "bidirectional"))
    )
    (net (code "68") (name "/U2_D9") (class "Default")
      (node (ref "CMOS1") (pin "A8") (pinfunction "A8_A8") (pintype "bidirectional"))
      (node (ref "CMOS2") (pin "D8") (pinfunction "8D_D8") (pintype "input"))
      (node (ref "CMOS3") (pin "D8") (pinfunction "8D_D8") (pintype "input"))
      (node (ref "CMOS4") (pin "D8") (pinfunction "8D_D8") (pintype "input"))
      (node (ref "U2") (pin "13") (pinfunction "PB1_13") (pintype "bidirectional"))
    )
    (net (code "69") (name "/U2_D10") (class "Default")
      (node (ref "CMOS1") (pin "G") (pinfunction "G_G") (pintype "input"))
      (node (ref "U2") (pin "14") (pinfunction "PB2_14") (pintype "bidirectional"))
    )
    (net (code "70") (name "/VBUS") (class "Default")
      (node (ref "F1") (pin "1") (pinfunction "1_1") (pintype "bidirectional"))
      (node (ref "J2") (pin "A4/B9") (pinfunction "VBUS_A4/B9") (pintype "power_in"))
      (node (ref "J2") (pin "B4/A9") (pinfunction "VBUS_B4/A9") (pintype "power_in"))
    )
    (net (code "71") (name "/VCC") (class "Default")
      (node (ref "C11") (pin "1") (pinfunction "1_1") (pintype "passive"))
      (node (ref "C2") (pin "2") (pinfunction "2_2") (pintype "passive"))
      (node (ref "C3") (pin "2") (pinfunction "2_2") (pintype "passive"))
      (node (ref "C5") (pin "2") (pinfunction "2_2") (pintype "passive"))
      (node (ref "C6") (pin "1") (pinfunction "1_1") (pintype "passive"))
      (node (ref "C7") (pin "2") (pinfunction "2_2") (pintype "passive"))
      (node (ref "CMOS1") (pin "VCC") (pinfunction "VCC_VCC") (pintype "bidirectional"))
      (node (ref "CMOS2") (pin "VCC") (pinfunction "VCC_VCC") (pintype "bidirectional"))
      (node (ref "CMOS3") (pin "VCC") (pinfunction "VCC_VCC") (pintype "bidirectional"))
      (node (ref "CMOS4") (pin "VCC") (pinfunction "VCC_VCC") (pintype "bidirectional"))
      (node (ref "CONNECTOR1") (pin "27") (pinfunction "VCC_27") (pintype "bidirectional"))
      (node (ref "CONNECTOR1") (pin "58") (pinfunction "VCC1_58") (pintype "bidirectional"))
      (node (ref "DI1") (pin "C") (pinfunction "C_C") (pintype "passive"))
      (node (ref "F1") (pin "2") (pinfunction "2_2") (pintype "bidirectional"))
      (node (ref "ICSP") (pin "2") (pinfunction "2_2") (pintype "passive"))
      (node (ref "R12") (pin "1") (pinfunction "1_1") (pintype "passive"))
      (node (ref "R13") (pin "1") (pinfunction "1_1") (pintype "passive"))
      (node (ref "R14") (pin "1") (pinfunction "1_1") (pintype "passive"))
      (node (ref "R15") (pin "1") (pinfunction "1_1") (pintype "passive"))
      (node (ref "R16") (pin "1") (pinfunction "1_1") (pintype "passive"))
      (node (ref "R17") (pin "1") (pinfunction "1_1") (pintype "passive"))
      (node (ref "R7") (pin "2") (pinfunction "2_2") (pintype "passive"))
      (node (ref "S1") (pin "1") (pinfunction "1_1") (pintype "bidirectional"))
      (node (ref "S1") (pin "2") (pinfunction "2_2") (pintype "bidirectional"))
      (node (ref "U1") (pin "7") (pinfunction "VCC_7") (pintype "power_in"))
      (node (ref "U2") (pin "18") (pinfunction "AVCC_18") (pintype "power_in"))
      (node (ref "U2") (pin "4") (pinfunction "VCC_4") (pintype "power_in"))
      (node (ref "U2") (pin "6") (pinfunction "VCC_6") (pintype "power_in"))
      (node (ref "U5") (pin "1") (pinfunction "VDD_1") (pintype "power_in"))
    )
    (net (code "72") (name "/VDD") (class "Default")
      (node (ref "C9") (pin "2") (pinfunction "2_2") (pintype "passive"))
      (node (ref "XTAL1") (pin "VDD") (pinfunction "VDD_VDD") (pintype "bidirectional"))
    )
    (net (code "73") (name "/VREF2") (class "Default")
      (node (ref "C12") (pin "2") (pinfunction "2_2") (pintype "passive"))
      (node (ref "R16") (pin "2") (pinfunction "2_2") (pintype "passive"))
      (node (ref "U4") (pin "7") (pinfunction "VREF2_7") (pintype "power_in"))
      (node (ref "U4") (pin "8") (pinfunction "ENABLE_8") (pintype "input"))
    )
    (net (code "74") (name "/XTAL_1") (class "Default")
      (node (ref "R9") (pin "1") (pinfunction "1_1") (pintype "passive"))
      (node (ref "U2") (pin "7") (pinfunction "PB6_7") (pintype "bidirectional"))
      (node (ref "Y1") (pin "3") (pinfunction "OUT_3") (pintype "output"))
    )
    (net (code "75") (name "/XTAL_2") (class "Default")
      (node (ref "R9") (pin "2") (pinfunction "2_2") (pintype "passive"))
      (node (ref "U2") (pin "8") (pinfunction "PB7_8") (pintype "bidirectional"))
      (node (ref "Y1") (pin "1") (pinfunction "IN_1") (pintype "input"))
    )
    (net (code "76") (name "GND") (class "Default")
      (node (ref "C1") (pin "2") (pinfunction "2_2") (pintype "passive"))
      (node (ref "C12") (pin "1") (pinfunction "1_1") (pintype "passive"))
      (node (ref "C13") (pin "1") (pinfunction "1_1") (pintype "passive"))
      (node (ref "C2") (pin "1") (pinfunction "1_1") (pintype "passive"))
      (node (ref "C3") (pin "1") (pinfunction "1_1") (pintype "passive"))
      (node (ref "C5") (pin "1") (pinfunction "1_1") (pintype "passive"))
      (node (ref "C6") (pin "2") (pinfunction "2_2") (pintype "passive"))
      (node (ref "C7") (pin "1") (pinfunction "1_1") (pintype "passive"))
      (node (ref "C8") (pin "1") (pinfunction "1_1") (pintype "passive"))
      (node (ref "C9") (pin "1") (pinfunction "1_1") (pintype "passive"))
      (node (ref "CIC_START") (pin "C") (pinfunction "C_C") (pintype "passive"))
      (node (ref "CMOS1") (pin "GND") (pinfunction "GND_GND") (pintype "bidirectional"))
      (node (ref "CMOS2") (pin "GND") (pinfunction "GND_GND") (pintype "bidirectional"))
      (node (ref "CMOS3") (pin "GND") (pinfunction "GND_GND") (pintype "bidirectional"))
      (node (ref "CMOS4") (pin "GND") (pinfunction "GND_GND") (pintype "bidirectional"))
      (node (ref "CONNECTOR1") (pin "33") (pinfunction "REFLESH_33") (pintype "bidirectional"))
      (node (ref "CONNECTOR1") (pin "36") (pinfunction "GND1_36") (pintype "bidirectional"))
      (node (ref "CONNECTOR1") (pin "5") (pinfunction "GND_5") (pintype "bidirectional"))
      (node (ref "ICSP") (pin "6") (pinfunction "6_6") (pintype "passive"))
      (node (ref "J2") (pin "A1/B12") (pinfunction "GND_A1/B12") (pintype "power_in"))
      (node (ref "J2") (pin "B1/A12") (pinfunction "GND_B1/A12") (pintype "power_in"))
      (node (ref "J2") (pin "S1") (pinfunction "GND_S1") (pintype "power_in"))
      (node (ref "J2") (pin "S2") (pinfunction "GND_S2") (pintype "power_in"))
      (node (ref "J2") (pin "S3") (pinfunction "GND_S3") (pintype "power_in"))
      (node (ref "J2") (pin "S4") (pinfunction "GND_S4") (pintype "power_in"))
      (node (ref "PW") (pin "C") (pinfunction "C_C") (pintype "passive"))
      (node (ref "R1") (pin "2") (pinfunction "2_2") (pintype "passive"))
      (node (ref "R2") (pin "2") (pinfunction "2_2") (pintype "passive"))
      (node (ref "R3") (pin "2") (pinfunction "2_2") (pintype "passive"))
      (node (ref "R8") (pin "1") (pinfunction "1_1") (pintype "passive"))
      (node (ref "RN1") (pin "10") (pinfunction "10_10") (pintype "passive"))
      (node (ref "RN1") (pin "11") (pinfunction "11_11") (pintype "passive"))
      (node (ref "RN1") (pin "12") (pinfunction "12_12") (pintype "passive"))
      (node (ref "RN1") (pin "13") (pinfunction "13_13") (pintype "passive"))
      (node (ref "RN1") (pin "14") (pinfunction "14_14") (pintype "passive"))
      (node (ref "RN1") (pin "15") (pinfunction "15_15") (pintype "passive"))
      (node (ref "RN1") (pin "16") (pinfunction "16_16") (pintype "passive"))
      (node (ref "RN1") (pin "9") (pinfunction "9_9") (pintype "passive"))
      (node (ref "RN2") (pin "10") (pinfunction "10_10") (pintype "passive"))
      (node (ref "RN2") (pin "11") (pinfunction "11_11") (pintype "passive"))
      (node (ref "RN2") (pin "12") (pinfunction "12_12") (pintype "passive"))
      (node (ref "RN2") (pin "13") (pinfunction "13_13") (pintype "passive"))
      (node (ref "RN2") (pin "14") (pinfunction "14_14") (pintype "passive"))
      (node (ref "RN2") (pin "15") (pinfunction "15_15") (pintype "passive"))
      (node (ref "RN2") (pin "16") (pinfunction "16_16") (pintype "passive"))
      (node (ref "RN2") (pin "9") (pinfunction "9_9") (pintype "passive"))
      (node (ref "RN3") (pin "10") (pinfunction "10_10") (pintype "passive"))
      (node (ref "RN3") (pin "11") (pinfunction "11_11") (pintype "passive"))
      (node (ref "RN3") (pin "12") (pinfunction "12_12") (pintype "passive"))
      (node (ref "RN3") (pin "13") (pinfunction "13_13") (pintype "passive"))
      (node (ref "RN3") (pin "14") (pinfunction "14_14") (pintype "passive"))
      (node (ref "RN3") (pin "15") (pinfunction "15_15") (pintype "passive"))
      (node (ref "RN3") (pin "16") (pinfunction "16_16") (pintype "passive"))
      (node (ref "RN3") (pin "9") (pinfunction "9_9") (pintype "passive"))
      (node (ref "RN4") (pin "10") (pinfunction "10_10") (pintype "passive"))
      (node (ref "RN4") (pin "11") (pinfunction "11_11") (pintype "passive"))
      (node (ref "RN4") (pin "12") (pinfunction "12_12") (pintype "passive"))
      (node (ref "RN4") (pin "13") (pinfunction "13_13") (pintype "passive"))
      (node (ref "RN4") (pin "14") (pinfunction "14_14") (pintype "passive"))
      (node (ref "RN4") (pin "15") (pinfunction "15_15") (pintype "passive"))
      (node (ref "RN4") (pin "16") (pinfunction "16_16") (pintype "passive"))
      (node (ref "RN4") (pin "9") (pinfunction "9_9") (pintype "passive"))
      (node (ref "RV1") (pin "2") (pinfunction "2_2") (pintype "passive"))
      (node (ref "RV2") (pin "2") (pinfunction "2_2") (pintype "passive"))
      (node (ref "S2") (pin "3") (pinfunction "3_3") (pintype "bidirectional"))
      (node (ref "S2") (pin "4") (pinfunction "4_4") (pintype "bidirectional"))
      (node (ref "U1") (pin "3") (pinfunction "GND_3") (pintype "power_in"))
      (node (ref "U2") (pin "21") (pinfunction "GND_21") (pintype "power_in"))
      (node (ref "U2") (pin "3") (pinfunction "GND_3") (pintype "power_in"))
      (node (ref "U2") (pin "5") (pinfunction "GND_5") (pintype "power_in"))
      (node (ref "U3") (pin "2") (pinfunction "GND_2") (pintype "power_in"))
      (node (ref "U4") (pin "4") (pinfunction "GND_4") (pintype "power_in"))
      (node (ref "U5") (pin "8") (pinfunction "VSS_8") (pintype "power_in"))
      (node (ref "XTAL1") (pin "GND") (pinfunction "GND_GND") (pintype "bidirectional"))
      (node (ref "Y1") (pin "2") (pinfunction "GND_2") (pintype "power_in"))
      (node (ref "Y2") (pin "2") (pinfunction "GND_2") (pintype "power_in"))
      (node (ref "Y2") (pin "4") (pinfunction "GND_4") (pintype "power_in"))
    )
    (net (code "77") (name "Net-(A0-PadC)") (class "Default")
      (node (ref "A0") (pin "C") (pinfunction "C_C") (pintype "passive"))
      (node (ref "RN3") (pin "1") (pinfunction "1_1") (pintype "passive"))
    )
    (net (code "78") (name "Net-(A1-PadC)") (class "Default")
      (node (ref "A1") (pin "C") (pinfunction "C_C") (pintype "passive"))
      (node (ref "RN3") (pin "2") (pinfunction "2_2") (pintype "passive"))
    )
    (net (code "79") (name "Net-(A2-PadC)") (class "Default")
      (node (ref "A2") (pin "C") (pinfunction "C_C") (pintype "passive"))
      (node (ref "RN3") (pin "3") (pinfunction "3_3") (pintype "passive"))
    )
    (net (code "80") (name "Net-(A3-PadC)") (class "Default")
      (node (ref "A3") (pin "C") (pinfunction "C_C") (pintype "passive"))
      (node (ref "RN3") (pin "4") (pinfunction "4_4") (pintype "passive"))
    )
    (net (code "81") (name "Net-(A4-PadC)") (class "Default")
      (node (ref "A4") (pin "C") (pinfunction "C_C") (pintype "passive"))
      (node (ref "RN3") (pin "5") (pinfunction "5_5") (pintype "passive"))
    )
    (net (code "82") (name "Net-(A5-PadC)") (class "Default")
      (node (ref "A5") (pin "C") (pinfunction "C_C") (pintype "passive"))
      (node (ref "RN3") (pin "6") (pinfunction "6_6") (pintype "passive"))
    )
    (net (code "83") (name "Net-(A6-PadC)") (class "Default")
      (node (ref "A6") (pin "C") (pinfunction "C_C") (pintype "passive"))
      (node (ref "RN3") (pin "7") (pinfunction "7_7") (pintype "passive"))
    )
    (net (code "84") (name "Net-(A7-PadC)") (class "Default")
      (node (ref "A7") (pin "C") (pinfunction "C_C") (pintype "passive"))
      (node (ref "RN3") (pin "8") (pinfunction "8_8") (pintype "passive"))
    )
    (net (code "85") (name "Net-(A8-PadC)") (class "Default")
      (node (ref "A8") (pin "C") (pinfunction "C_C") (pintype "passive"))
      (node (ref "RN2") (pin "1") (pinfunction "1_1") (pintype "passive"))
    )
    (net (code "86") (name "Net-(A9-PadC)") (class "Default")
      (node (ref "A9") (pin "C") (pinfunction "C_C") (pintype "passive"))
      (node (ref "RN2") (pin "2") (pinfunction "2_2") (pintype "passive"))
    )
    (net (code "87") (name "Net-(A10-PadC)") (class "Default")
      (node (ref "A10") (pin "C") (pinfunction "C_C") (pintype "passive"))
      (node (ref "RN2") (pin "3") (pinfunction "3_3") (pintype "passive"))
    )
    (net (code "88") (name "Net-(A11-PadC)") (class "Default")
      (node (ref "A11") (pin "C") (pinfunction "C_C") (pintype "passive"))
      (node (ref "RN2") (pin "4") (pinfunction "4_4") (pintype "passive"))
    )
    (net (code "89") (name "Net-(A12-PadC)") (class "Default")
      (node (ref "A12") (pin "C") (pinfunction "C_C") (pintype "passive"))
      (node (ref "RN2") (pin "5") (pinfunction "5_5") (pintype "passive"))
    )
    (net (code "90") (name "Net-(A13-PadC)") (class "Default")
      (node (ref "A13") (pin "C") (pinfunction "C_C") (pintype "passive"))
      (node (ref "RN2") (pin "6") (pinfunction "6_6") (pintype "passive"))
    )
    (net (code "91") (name "Net-(A14-PadC)") (class "Default")
      (node (ref "A14") (pin "C") (pinfunction "C_C") (pintype "passive"))
      (node (ref "RN2") (pin "7") (pinfunction "7_7") (pintype "passive"))
    )
    (net (code "92") (name "Net-(A15-PadC)") (class "Default")
      (node (ref "A15") (pin "C") (pinfunction "C_C") (pintype "passive"))
      (node (ref "RN2") (pin "8") (pinfunction "8_8") (pintype "passive"))
    )
    (net (code "93") (name "Net-(A16-PadC)") (class "Default")
      (node (ref "A16") (pin "C") (pinfunction "C_C") (pintype "passive"))
      (node (ref "RN4") (pin "1") (pinfunction "1_1") (pintype "passive"))
    )
    (net (code "94") (name "Net-(A17-PadC)") (class "Default")
      (node (ref "A17") (pin "C") (pinfunction "C_C") (pintype "passive"))
      (node (ref "RN4") (pin "2") (pinfunction "2_2") (pintype "passive"))
    )
    (net (code "95") (name "Net-(A18-PadC)") (class "Default")
      (node (ref "A18") (pin "C") (pinfunction "C_C") (pintype "passive"))
      (node (ref "RN4") (pin "3") (pinfunction "3_3") (pintype "passive"))
    )
    (net (code "96") (name "Net-(A19-PadC)") (class "Default")
      (node (ref "A19") (pin "C") (pinfunction "C_C") (pintype "passive"))
      (node (ref "RN4") (pin "4") (pinfunction "4_4") (pintype "passive"))
    )
    (net (code "97") (name "Net-(A20-PadC)") (class "Default")
      (node (ref "A20") (pin "C") (pinfunction "C_C") (pintype "passive"))
      (node (ref "RN4") (pin "5") (pinfunction "5_5") (pintype "passive"))
    )
    (net (code "98") (name "Net-(A21-PadC)") (class "Default")
      (node (ref "A21") (pin "C") (pinfunction "C_C") (pintype "passive"))
      (node (ref "RN4") (pin "6") (pinfunction "6_6") (pintype "passive"))
    )
    (net (code "99") (name "Net-(A22-PadC)") (class "Default")
      (node (ref "A22") (pin "C") (pinfunction "C_C") (pintype "passive"))
      (node (ref "RN4") (pin "7") (pinfunction "7_7") (pintype "passive"))
    )
    (net (code "100") (name "Net-(A23-PadC)") (class "Default")
      (node (ref "A23") (pin "C") (pinfunction "C_C") (pintype "passive"))
      (node (ref "RN4") (pin "8") (pinfunction "8_8") (pintype "passive"))
    )
    (net (code "101") (name "Net-(C8-Pad2)") (class "Default")
      (node (ref "C8") (pin "2") (pinfunction "2_2") (pintype "passive"))
      (node (ref "XTAL1") (pin "VDDO") (pinfunction "VDDO_VDDO") (pintype "bidirectional"))
    )
    (net (code "102") (name "Net-(CIC_START-PadA)") (class "Default")
      (node (ref "CIC_START") (pin "A") (pinfunction "A_A") (pintype "passive"))
      (node (ref "R6") (pin "2") (pinfunction "2_2") (pintype "passive"))
    )
    (net (code "103") (name "Net-(D0-PadC)") (class "Default")
      (node (ref "D0") (pin "C") (pinfunction "C_C") (pintype "passive"))
      (node (ref "RN1") (pin "1") (pinfunction "1_1") (pintype "passive"))
    )
    (net (code "104") (name "Net-(D1-PadC)") (class "Default")
      (node (ref "D1") (pin "C") (pinfunction "C_C") (pintype "passive"))
      (node (ref "RN1") (pin "2") (pinfunction "2_2") (pintype "passive"))
    )
    (net (code "105") (name "Net-(D2-PadC)") (class "Default")
      (node (ref "D2") (pin "C") (pinfunction "C_C") (pintype "passive"))
      (node (ref "RN1") (pin "3") (pinfunction "3_3") (pintype "passive"))
    )
    (net (code "106") (name "Net-(D3-PadC)") (class "Default")
      (node (ref "D3") (pin "C") (pinfunction "C_C") (pintype "passive"))
      (node (ref "RN1") (pin "4") (pinfunction "4_4") (pintype "passive"))
    )
    (net (code "107") (name "Net-(D4-PadC)") (class "Default")
      (node (ref "D4") (pin "C") (pinfunction "C_C") (pintype "passive"))
      (node (ref "RN1") (pin "5") (pinfunction "5_5") (pintype "passive"))
    )
    (net (code "108") (name "Net-(D5-PadC)") (class "Default")
      (node (ref "D5") (pin "C") (pinfunction "C_C") (pintype "passive"))
      (node (ref "RN1") (pin "6") (pinfunction "6_6") (pintype "passive"))
    )
    (net (code "109") (name "Net-(D6-PadC)") (class "Default")
      (node (ref "D6") (pin "C") (pinfunction "C_C") (pintype "passive"))
      (node (ref "RN1") (pin "7") (pinfunction "7_7") (pintype "passive"))
    )
    (net (code "110") (name "Net-(D7-PadC)") (class "Default")
      (node (ref "D7") (pin "C") (pinfunction "C_C") (pintype "passive"))
      (node (ref "RN1") (pin "8") (pinfunction "8_8") (pintype "passive"))
    )
    (net (code "111") (name "Net-(J2-CC1)") (class "Default")
      (node (ref "J2") (pin "A5") (pinfunction "CC1_A5") (pintype "bidirectional"))
      (node (ref "R2") (pin "1") (pinfunction "1_1") (pintype "passive"))
    )
    (net (code "112") (name "Net-(J2-CC2)") (class "Default")
      (node (ref "J2") (pin "B5") (pinfunction "CC2_B5") (pintype "bidirectional"))
      (node (ref "R3") (pin "1") (pinfunction "1_1") (pintype "passive"))
    )
    (net (code "113") (name "Net-(PW-PadA)") (class "Default")
      (node (ref "PW") (pin "A") (pinfunction "A_A") (pintype "passive"))
      (node (ref "R14") (pin "2") (pinfunction "2_2") (pintype "passive"))
    )
    (net (code "114") (name "Net-(R1-Pad1)") (class "Default")
      (node (ref "R1") (pin "1") (pinfunction "1_1") (pintype "passive"))
      (node (ref "S1") (pin "3") (pinfunction "3_3") (pintype "bidirectional"))
    )
    (net (code "115") (name "Net-(R12-Pad2)") (class "Default")
      (node (ref "R12") (pin "2") (pinfunction "2_2") (pintype "passive"))
      (node (ref "TX") (pin "A") (pinfunction "A_A") (pintype "passive"))
    )
    (net (code "116") (name "Net-(R13-Pad2)") (class "Default")
      (node (ref "R13") (pin "2") (pinfunction "2_2") (pintype "passive"))
      (node (ref "RX") (pin "A") (pinfunction "A_A") (pintype "passive"))
    )
    (net (code "117") (name "Net-(U1-RX)") (class "Default")
      (node (ref "R11") (pin "2") (pinfunction "2_2") (pintype "passive"))
      (node (ref "U1") (pin "9") (pinfunction "RX_9") (pintype "input"))
    )
    (net (code "118") (name "Net-(U1-TX)") (class "Default")
      (node (ref "R10") (pin "2") (pinfunction "2_2") (pintype "passive"))
      (node (ref "U1") (pin "8") (pinfunction "TX_8") (pintype "output"))
    )
    (net (code "119") (name "Net-(U1-V3)") (class "Default")
      (node (ref "C1") (pin "1") (pinfunction "1_1") (pintype "passive"))
      (node (ref "U1") (pin "10") (pinfunction "V3_10") (pintype "power_in"))
    )
    (net (code "120") (name "Net-(U3-VIN)") (class "Default")
      (node (ref "C11") (pin "2") (pinfunction "2_2") (pintype "passive"))
      (node (ref "U3") (pin "1") (pinfunction "VIN_1") (pintype "input"))
    )
    (net (code "121") (name "Net-(U3-VOUT)") (class "Default")
      (node (ref "C10") (pin "1") (pinfunction "1_1") (pintype "passive"))
      (node (ref "U3") (pin "3") (pinfunction "VOUT_3") (pintype "output"))
    )
    (net (code "122") (name "Net-(U5-GP3{slash}*MCLR{slash}VPP)") (class "Default")
      (node (ref "S1") (pin "4") (pinfunction "4_4") (pintype "bidirectional"))
      (node (ref "U5") (pin "4") (pinfunction "GP3/*MCLR/VPP_4") (pintype "bidirectional"))
    )
    (net (code "123") (name "Net-(XTAL1-PadXA)") (class "Default")
      (node (ref "XTAL1") (pin "XA") (pinfunction "XA_XA") (pintype "bidirectional"))
      (node (ref "Y2") (pin "3") (pinfunction "3_3") (pintype "passive"))
    )
    (net (code "124") (name "Net-(XTAL1-PadXB)") (class "Default")
      (node (ref "XTAL1") (pin "XB") (pinfunction "XB_XB") (pintype "bidirectional"))
      (node (ref "Y2") (pin "1") (pinfunction "1_1") (pintype "passive"))
    )
    (net (code "125") (name "unconnected-(CONNECTOR1-EXPAND-Pad2)") (class "Default")
      (node (ref "CONNECTOR1") (pin "2") (pinfunction "EXPAND_2") (pintype "bidirectional"))
    )
    (net (code "126") (name "unconnected-(CONNECTOR1-L_AUDIO-Pad31)") (class "Default")
      (node (ref "CONNECTOR1") (pin "31") (pinfunction "L_AUDIO_31") (pintype "bidirectional"))
    )
    (net (code "127") (name "unconnected-(CONNECTOR1-PA0-Pad28)") (class "Default")
      (node (ref "CONNECTOR1") (pin "28") (pinfunction "PA0_28") (pintype "bidirectional"))
    )
    (net (code "128") (name "unconnected-(CONNECTOR1-PA1-Pad59)") (class "Default")
      (node (ref "CONNECTOR1") (pin "59") (pinfunction "PA1_59") (pintype "bidirectional"))
    )
    (net (code "129") (name "unconnected-(CONNECTOR1-PA2-Pad29)") (class "Default")
      (node (ref "CONNECTOR1") (pin "29") (pinfunction "PA2_29") (pintype "bidirectional"))
    )
    (net (code "130") (name "unconnected-(CONNECTOR1-PA3-Pad60)") (class "Default")
      (node (ref "CONNECTOR1") (pin "60") (pinfunction "PA3_60") (pintype "bidirectional"))
    )
    (net (code "131") (name "unconnected-(CONNECTOR1-PA4-Pad30)") (class "Default")
      (node (ref "CONNECTOR1") (pin "30") (pinfunction "PA4_30") (pintype "bidirectional"))
    )
    (net (code "132") (name "unconnected-(CONNECTOR1-PA5-Pad61)") (class "Default")
      (node (ref "CONNECTOR1") (pin "61") (pinfunction "PA5_61") (pintype "bidirectional"))
    )
    (net (code "133") (name "unconnected-(CONNECTOR1-PA6-Pad3)") (class "Default")
      (node (ref "CONNECTOR1") (pin "3") (pinfunction "PA6_3") (pintype "bidirectional"))
    )
    (net (code "134") (name "unconnected-(CONNECTOR1-PA7-Pad34)") (class "Default")
      (node (ref "CONNECTOR1") (pin "34") (pinfunction "PA7_34") (pintype "bidirectional"))
    )
    (net (code "135") (name "unconnected-(CONNECTOR1-R_AUDIO-Pad62)") (class "Default")
      (node (ref "CONNECTOR1") (pin "62") (pinfunction "R_AUDIO_62") (pintype "bidirectional"))
    )
    (net (code "136") (name "unconnected-(CONNECTOR1-{slash}IRQ-Pad18)") (class "Default")
      (node (ref "CONNECTOR1") (pin "18") (pinfunction "/IRQ_18") (pintype "bidirectional"))
    )
    (net (code "137") (name "unconnected-(CONNECTOR1-{slash}PARD-Pad4)") (class "Default")
      (node (ref "CONNECTOR1") (pin "4") (pinfunction "/PARD_4") (pintype "bidirectional"))
    )
    (net (code "138") (name "unconnected-(CONNECTOR1-{slash}PAWR-Pad35)") (class "Default")
      (node (ref "CONNECTOR1") (pin "35") (pinfunction "/PAWR_35") (pintype "bidirectional"))
    )
    (net (code "139") (name "unconnected-(CONNECTOR1-{slash}WARM-Pad32)") (class "Default")
      (node (ref "CONNECTOR1") (pin "32") (pinfunction "/WARM_32") (pintype "bidirectional"))
    )
    (net (code "140") (name "unconnected-(J2-SBU1-PadA8)") (class "Default")
      (node (ref "J2") (pin "A8") (pinfunction "SBU1_A8") (pintype "bidirectional"))
    )
    (net (code "141") (name "unconnected-(J2-SBU2-PadB8)") (class "Default")
      (node (ref "J2") (pin "B8") (pinfunction "SBU2_B8") (pintype "bidirectional"))
    )
    (net (code "142") (name "unconnected-(U1-CTS-Pad5)") (class "Default")
      (node (ref "U1") (pin "5") (pinfunction "CTS_5") (pintype "input"))
    )
    (net (code "143") (name "unconnected-(U1-TNOW-Pad6)") (class "Default")
      (node (ref "U1") (pin "6") (pinfunction "TNOW_6") (pintype "output"))
    )
    (net (code "144") (name "unconnected-(U2-ADC6-Pad19)") (class "Default")
      (node (ref "U2") (pin "19") (pinfunction "ADC6_19") (pintype "bidirectional"))
    )
    (net (code "145") (name "unconnected-(U2-ADC7-Pad22)") (class "Default")
      (node (ref "U2") (pin "22") (pinfunction "ADC7_22") (pintype "bidirectional"))
    )
    (net (code "146") (name "unconnected-(U2-AREF-Pad20)") (class "Default")
      (node (ref "U2") (pin "20") (pinfunction "AREF_20") (pintype "input"))
    )
  )
)
